# Power_Protection.net
KiCad netlist of a schematic drawn in Altium Designer
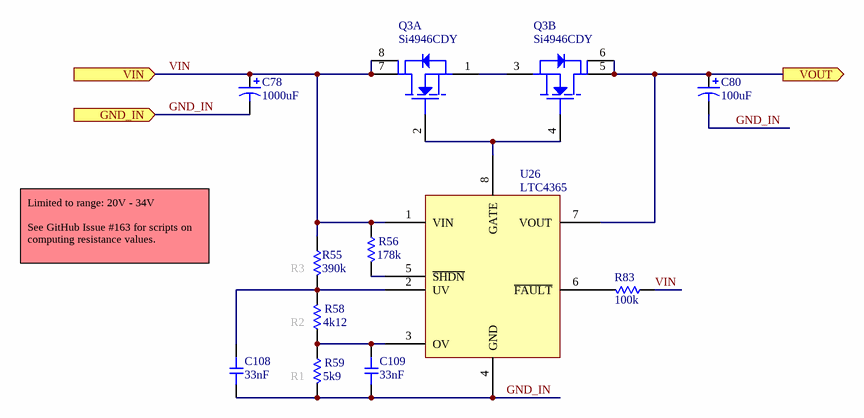
[diagram p0: Power_Protection.SchDoc]

(export (version "E")
  (design (tool "Eeschema 10.0.6"))
  (components
    (comp (ref "C78")
      (value "1000uF")
      (footprint "CAP - UVR1H102MHD1TO")
      (description "Polarized Capacitor (Radial)")
      (fields (field (name "Comment") "Cap Pol1"))
      (libsource (lib "Miscellaneous Devices") (part "Cap Pol1"))
    )
    (comp (ref "C80")
      (value "100uF")
      (footprint "CAP - UWT1V101MCL1GS")
      (description "Polarized Capacitor (Radial)")
      (fields (field (name "Comment") "Cap Pol1"))
      (libsource (lib "Miscellaneous Devices") (part "Cap Pol1"))
    )
    (comp (ref "C108")
      (value "33nF")
      (footprint "0603-CAP")
      (description "Capacitor")
      (libsource (lib "AMDC") (part "Capacitor"))
    )
    (comp (ref "C109")
      (value "33nF")
      (footprint "0603-CAP")
      (description "Capacitor")
      (libsource (lib "AMDC") (part "Capacitor"))
    )
    (comp (ref "Q3")
      (value "Si4946CDY")
      (footprint "SOIC127P600X175-8N")
      (description "MOSFET N-CHAN DUAL 60V SO-8")
      (libsource (lib "AMDC") (part "SI4946CDY-T1-GE3"))
    )
    (comp (ref "R55")
      (value "390k")
      (footprint "0603-RES")
      (description "Resistor")
      (libsource (lib "AMDC") (part "Resistor"))
    )
    (comp (ref "R56")
      (value "178k")
      (footprint "0603-RES")
      (description "Resistor")
      (libsource (lib "AMDC") (part "Resistor"))
    )
    (comp (ref "R58")
      (value "4k12")
      (footprint "0603-RES")
      (description "Resistor")
      (libsource (lib "AMDC") (part "Resistor"))
    )
    (comp (ref "R59")
      (value "5k9")
      (footprint "0603-RES")
      (description "Resistor")
      (libsource (lib "AMDC") (part "Resistor"))
    )
    (comp (ref "R83")
      (value "100k")
      (footprint "0603-RES")
      (description "Resistor")
      (libsource (lib "AMDC") (part "Resistor"))
    )
    (comp (ref "U26")
      (value "LTC4365")
      (footprint "TSOP65P280X100-8N")
      (description "IC OVERVOLTAGE PROT TSOT23-8")
      (libsource (lib "AMDC") (part "LTC4365CTS8#TRMPBF"))
    )
  )
  (nets
    (net (code "1") (name "/GND_IN") (class "Default")
      (node (ref "C108") (pin "2") (pinfunction "2_2") (pintype "passive"))
      (node (ref "C109") (pin "2") (pinfunction "2_2") (pintype "passive"))
      (node (ref "C78") (pin "2") (pinfunction "2_2") (pintype "passive"))
      (node (ref "C80") (pin "2") (pinfunction "2_2") (pintype "passive"))
      (node (ref "R59") (pin "2") (pinfunction "2_2") (pintype "passive"))
      (node (ref "U26") (pin "4") (pinfunction "GND_4") (pintype "passive"))
    )
    (net (code "2") (name "/VIN") (class "Default")
      (node (ref "C78") (pin "1") (pinfunction "1_1") (pintype "passive"))
      (node (ref "Q3") (pin "7") (pinfunction "D1_7") (pintype "passive"))
      (node (ref "Q3") (pin "8") (pinfunction "D1_8") (pintype "passive"))
      (node (ref "R55") (pin "1") (pinfunction "1_1") (pintype "passive"))
      (node (ref "R56") (pin "1") (pinfunction "1_1") (pintype "passive"))
      (node (ref "R83") (pin "1") (pinfunction "1_1") (pintype "passive"))
      (node (ref "U26") (pin "1") (pinfunction "VIN_1") (pintype "passive"))
    )
    (net (code "3") (name "/VOUT") (class "Default")
      (node (ref "C80") (pin "1") (pinfunction "1_1") (pintype "passive"))
      (node (ref "Q3") (pin "5") (pinfunction "D2_5") (pintype "passive"))
      (node (ref "Q3") (pin "6") (pinfunction "D2_6") (pintype "passive"))
      (node (ref "U26") (pin "7") (pinfunction "VOUT_7") (pintype "passive"))
    )
    (net (code "4") (name "Net-(Q3A-G1)") (class "Default")
      (node (ref "Q3") (pin "2") (pinfunction "G1_2") (pintype "passive"))
      (node (ref "Q3") (pin "4") (pinfunction "G2_4") (pintype "passive"))
      (node (ref "U26") (pin "8") (pinfunction "GATE_8") (pintype "passive"))
    )
    (net (code "5") (name "Net-(Q3A-S1)") (class "Default")
      (node (ref "Q3") (pin "1") (pinfunction "S1_1") (pintype "passive"))
      (node (ref "Q3") (pin "3") (pinfunction "S2_3") (pintype "passive"))
    )
    (net (code "6") (name "Net-(U26-OV)") (class "Default")
      (node (ref "C109") (pin "1") (pinfunction "1_1") (pintype "passive"))
      (node (ref "R58") (pin "1") (pinfunction "1_1") (pintype "passive"))
      (node (ref "R59") (pin "1") (pinfunction "1_1") (pintype "passive"))
      (node (ref "U26") (pin "3") (pinfunction "OV_3") (pintype "passive"))
    )
    (net (code "7") (name "Net-(U26-UV)") (class "Default")
      (node (ref "C108") (pin "1") (pinfunction "1_1") (pintype "passive"))
      (node (ref "R55") (pin "2") (pinfunction "2_2") (pintype "passive"))
      (node (ref "R58") (pin "2") (pinfunction "2_2") (pintype "passive"))
      (node (ref "U26") (pin "2") (pinfunction "UV_2") (pintype "passive"))
    )
    (net (code "8") (name "Net-(U26-~{FAULT})") (class "Default")
      (node (ref "R83") (pin "2") (pinfunction "2_2") (pintype "passive"))
      (node (ref "U26") (pin "6") (pinfunction "~{FAULT}_6") (pintype "passive"))
    )
    (net (code "9") (name "Net-(U26-~{SHDN})") (class "Default")
      (node (ref "R56") (pin "2") (pinfunction "2_2") (pintype "passive"))
      (node (ref "U26") (pin "5") (pinfunction "~{SHDN}_5") (pintype "passive"))
    )
  )
)
